# hd-hdr-alt.net
KiCad netlist of a schematic drawn in Altium Designer
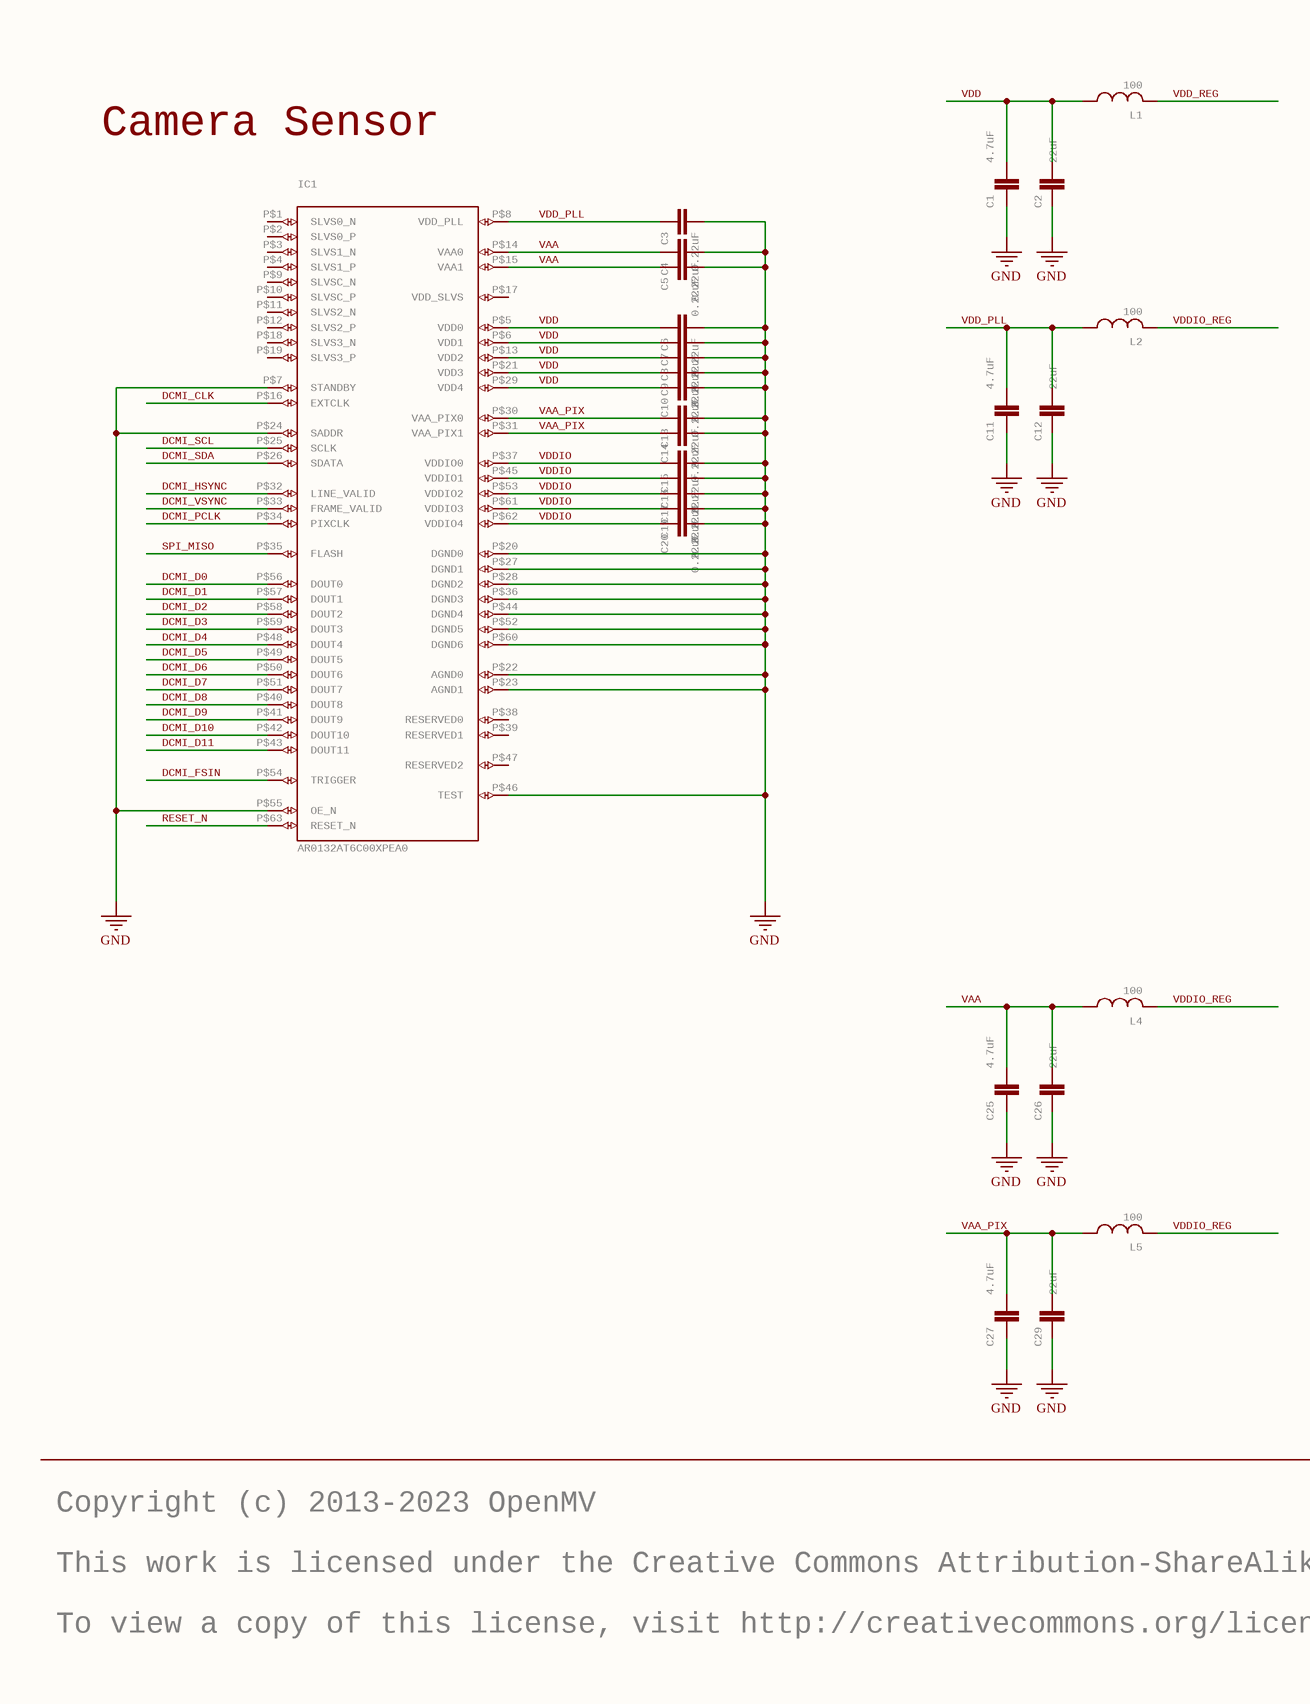
[diagram p0: hd-hdr-alt.SchDoc, left]
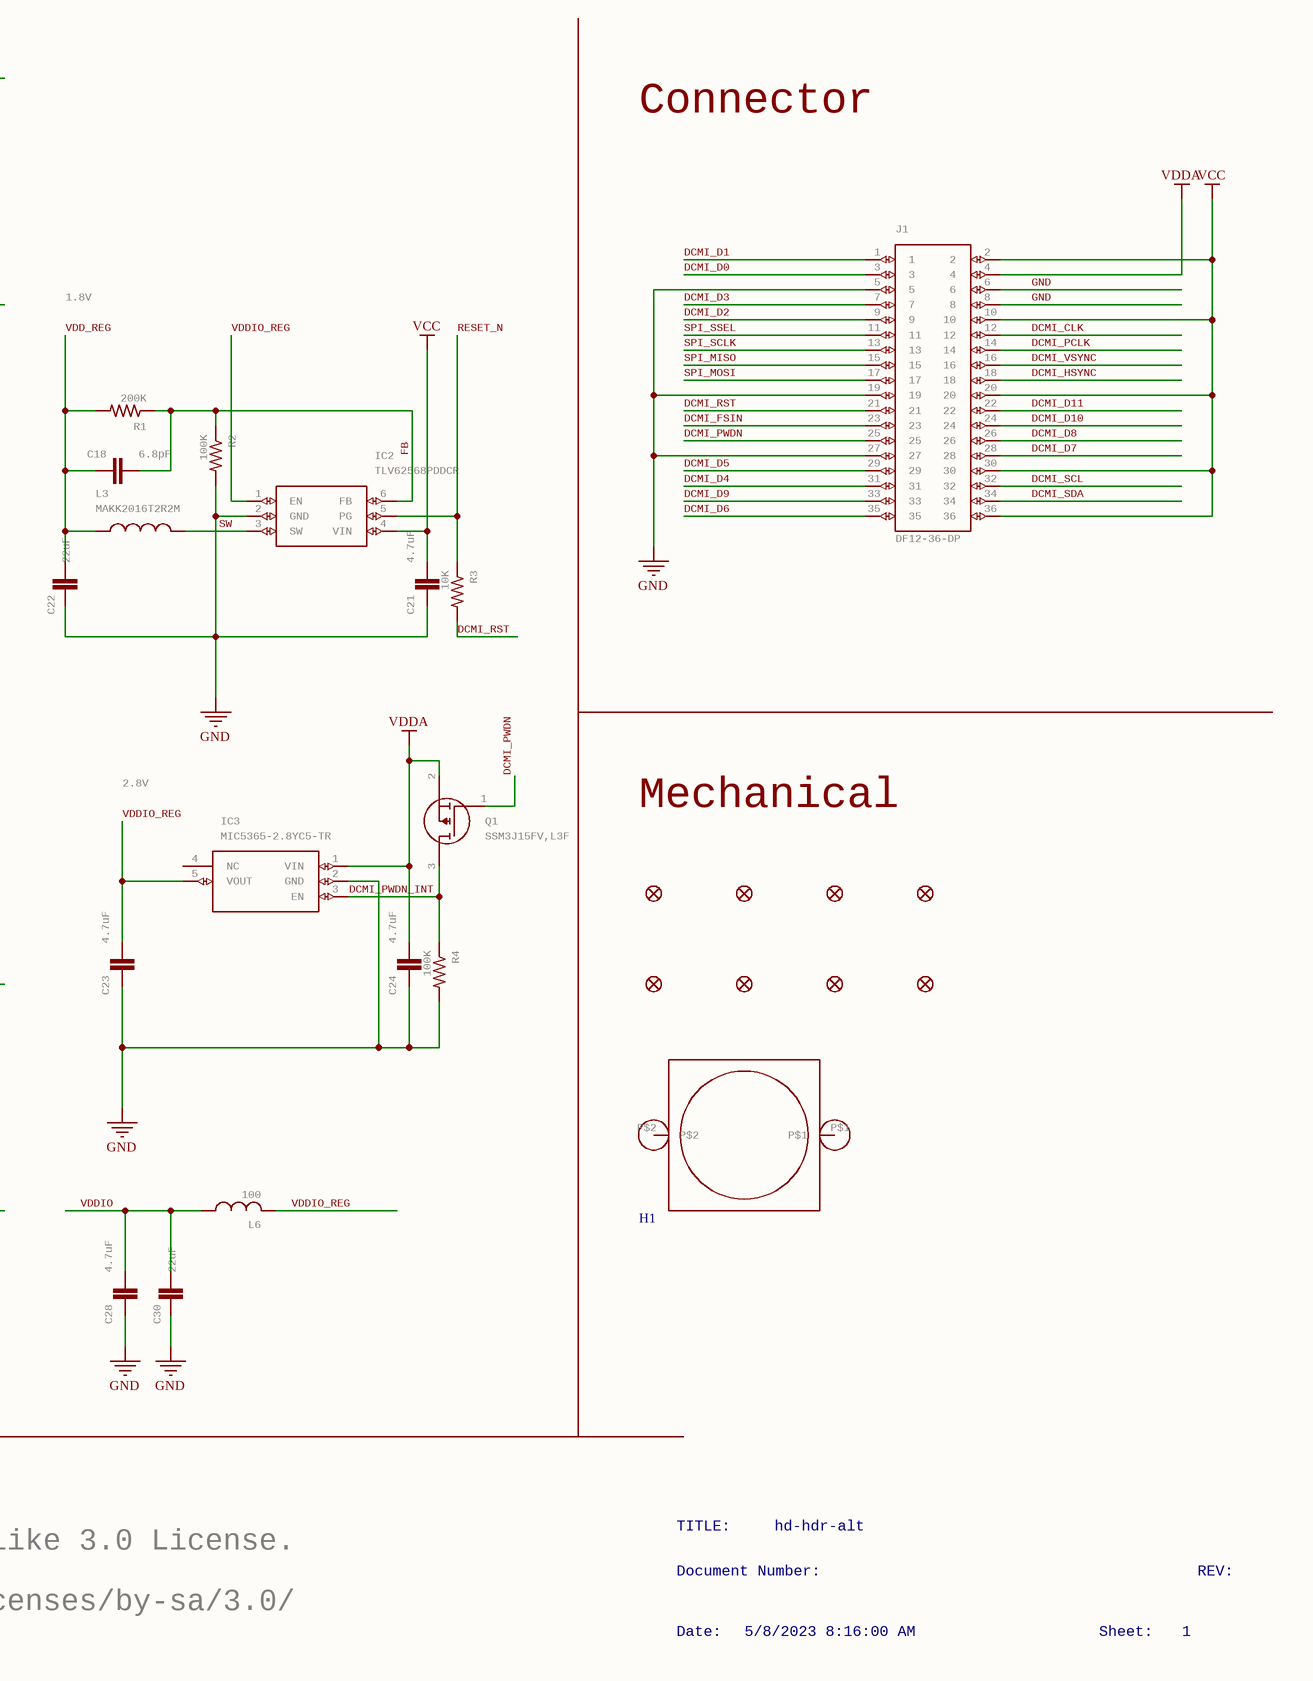
[diagram p1: hd-hdr-alt.SchDoc, right]

(export (version "E")
  (design (tool "Eeschema 10.0.6"))
  (components
    (comp (ref "C1")
      (value "4.7uF")
      (footprint "0402")
      (description "0402 (1005 Metric) Nick Garner - TeleSense")
      (fields (field (name "MPN") "JMK105BBJ475MV-F"))
      (libsource (lib "0402") (part "CAP_0402"))
    )
    (comp (ref "C2")
      (value "22uF")
      (footprint "0805")
      (fields (field (name "MPN") "CL21A226MQQNNNE"))
      (libsource (lib "SparkFun-Capacitors") (part "22UF-0805-6.3V-20%"))
    )
    (comp (ref "C3")
      (value "0.22uF")
      (footprint "C0201")
      (description "CAPACITOR, European symbol")
      (fields (field (name "MPN") "GRM033R60J224ME15D"))
      (libsource (lib "rcl") (part "C-EUC0201"))
    )
    (comp (ref "C4")
      (value "0.22uF")
      (footprint "C0201")
      (description "CAPACITOR, European symbol")
      (fields (field (name "MPN") "GRM033R60J224ME15D"))
      (libsource (lib "rcl") (part "C-EUC0201"))
    )
    (comp (ref "C5")
      (value "0.22uF")
      (footprint "C0201")
      (description "CAPACITOR, European symbol")
      (fields (field (name "MPN") "GRM033R60J224ME15D"))
      (libsource (lib "rcl") (part "C-EUC0201"))
    )
    (comp (ref "C6")
      (value "0.22uF")
      (footprint "C0201")
      (description "CAPACITOR, European symbol")
      (fields (field (name "MPN") "GRM033R60J224ME15D"))
      (libsource (lib "rcl") (part "C-EUC0201"))
    )
    (comp (ref "C7")
      (value "0.22uF")
      (footprint "C0201")
      (description "CAPACITOR, European symbol")
      (fields (field (name "MPN") "GRM033R60J224ME15D"))
      (libsource (lib "rcl") (part "C-EUC0201"))
    )
    (comp (ref "C8")
      (value "0.22uF")
      (footprint "C0201")
      (description "CAPACITOR, European symbol")
      (fields (field (name "MPN") "GRM033R60J224ME15D"))
      (libsource (lib "rcl") (part "C-EUC0201"))
    )
    (comp (ref "C9")
      (value "0.22uF")
      (footprint "C0201")
      (description "CAPACITOR, European symbol")
      (fields (field (name "MPN") "GRM033R60J224ME15D"))
      (libsource (lib "rcl") (part "C-EUC0201"))
    )
    (comp (ref "C10")
      (value "0.22uF")
      (footprint "C0201")
      (description "CAPACITOR, European symbol")
      (fields (field (name "MPN") "GRM033R60J224ME15D"))
      (libsource (lib "rcl") (part "C-EUC0201"))
    )
    (comp (ref "C11")
      (value "4.7uF")
      (footprint "0402")
      (description "0402 (1005 Metric) Nick Garner - TeleSense")
      (fields (field (name "MPN") "JMK105BBJ475MV-F"))
      (libsource (lib "0402") (part "CAP_0402"))
    )
    (comp (ref "C12")
      (value "22uF")
      (footprint "0805")
      (fields (field (name "MPN") "CL21A226MQQNNNE"))
      (libsource (lib "SparkFun-Capacitors") (part "22UF-0805-6.3V-20%"))
    )
    (comp (ref "C13")
      (value "0.22uF")
      (footprint "C0201")
      (description "CAPACITOR, European symbol")
      (fields (field (name "MPN") "GRM033R60J224ME15D"))
      (libsource (lib "rcl") (part "C-EUC0201"))
    )
    (comp (ref "C14")
      (value "0.22uF")
      (footprint "C0201")
      (description "CAPACITOR, European symbol")
      (fields (field (name "MPN") "GRM033R60J224ME15D"))
      (libsource (lib "rcl") (part "C-EUC0201"))
    )
    (comp (ref "C15")
      (value "0.22uF")
      (footprint "C0201")
      (description "CAPACITOR, European symbol")
      (fields (field (name "MPN") "GRM033R60J224ME15D"))
      (libsource (lib "rcl") (part "C-EUC0201"))
    )
    (comp (ref "C16")
      (value "0.22uF")
      (footprint "C0201")
      (description "CAPACITOR, European symbol")
      (fields (field (name "MPN") "GRM033R60J224ME15D"))
      (libsource (lib "rcl") (part "C-EUC0201"))
    )
    (comp (ref "C17")
      (value "0.22uF")
      (footprint "C0201")
      (description "CAPACITOR, European symbol")
      (fields (field (name "MPN") "GRM033R60J224ME15D"))
      (libsource (lib "rcl") (part "C-EUC0201"))
    )
    (comp (ref "C18")
      (value "6.8pF")
      (footprint "0402")
      (description "0402 (1005 Metric) Nick Garner - TeleSense")
      (fields (field (name "MPN") "GRM1555C1H6R8DA01D"))
      (libsource (lib "") (part "CAP_0402_1"))
    )
    (comp (ref "C19")
      (value "0.22uF")
      (footprint "C0201")
      (description "CAPACITOR, European symbol")
      (fields (field (name "MPN") "GRM033R60J224ME15D"))
      (libsource (lib "rcl") (part "C-EUC0201"))
    )
    (comp (ref "C20")
      (value "0.22uF")
      (footprint "C0201")
      (description "CAPACITOR, European symbol")
      (fields (field (name "MPN") "GRM033R60J224ME15D"))
      (libsource (lib "rcl") (part "C-EUC0201"))
    )
    (comp (ref "C21")
      (value "4.7uF")
      (footprint "0402")
      (description "0402 (1005 Metric) Nick Garner - TeleSense")
      (fields (field (name "MPN") "JMK105BBJ475MV-F"))
      (libsource (lib "0402") (part "CAP_0402"))
    )
    (comp (ref "C22")
      (value "22uF")
      (footprint "0805")
      (fields (field (name "MPN") "CL21A226MQQNNNE"))
      (libsource (lib "SparkFun-Capacitors") (part "22UF-0805-6.3V-20%"))
    )
    (comp (ref "C23")
      (value "4.7uF")
      (footprint "0402")
      (description "0402 (1005 Metric) Nick Garner - TeleSense")
      (fields (field (name "MPN") "JMK105BBJ475MV-F"))
      (libsource (lib "0402") (part "CAP_0402"))
    )
    (comp (ref "C24")
      (value "4.7uF")
      (footprint "0402")
      (description "0402 (1005 Metric) Nick Garner - TeleSense")
      (fields (field (name "MPN") "JMK105BBJ475MV-F"))
      (libsource (lib "0402") (part "CAP_0402"))
    )
    (comp (ref "C25")
      (value "4.7uF")
      (footprint "0402")
      (description "0402 (1005 Metric) Nick Garner - TeleSense")
      (fields (field (name "MPN") "JMK105BBJ475MV-F"))
      (libsource (lib "0402") (part "CAP_0402"))
    )
    (comp (ref "C26")
      (value "22uF")
      (footprint "0805")
      (fields (field (name "MPN") "CL21A226MQQNNNE"))
      (libsource (lib "SparkFun-Capacitors") (part "22UF-0805-6.3V-20%"))
    )
    (comp (ref "C27")
      (value "4.7uF")
      (footprint "0402")
      (description "0402 (1005 Metric) Nick Garner - TeleSense")
      (fields (field (name "MPN") "JMK105BBJ475MV-F"))
      (libsource (lib "0402") (part "CAP_0402"))
    )
    (comp (ref "C28")
      (value "4.7uF")
      (footprint "0402")
      (description "0402 (1005 Metric) Nick Garner - TeleSense")
      (fields (field (name "MPN") "JMK105BBJ475MV-F"))
      (libsource (lib "0402") (part "CAP_0402"))
    )
    (comp (ref "C29")
      (value "22uF")
      (footprint "0805")
      (fields (field (name "MPN") "CL21A226MQQNNNE"))
      (libsource (lib "SparkFun-Capacitors") (part "22UF-0805-6.3V-20%"))
    )
    (comp (ref "C30")
      (value "22uF")
      (footprint "0805")
      (fields (field (name "MPN") "CL21A226MQQNNNE"))
      (libsource (lib "SparkFun-Capacitors") (part "22UF-0805-6.3V-20%"))
    )
    (comp (ref "FD1")
      (value "FIDUCIAL1X2")
      (footprint "FIDUCIAL-1X2")
      (fields (field (name "LIBRARYNAME") "SparkFun-Aesthetics"))
      (libsource (lib "SparkFun-Aesthetics") (part "FIDUCIAL1X2"))
    )
    (comp (ref "FD2")
      (value "FIDUCIAL1X2")
      (footprint "FIDUCIAL-1X2")
      (fields (field (name "LIBRARYNAME") "SparkFun-Aesthetics"))
      (libsource (lib "SparkFun-Aesthetics") (part "FIDUCIAL1X2"))
    )
    (comp (ref "FD3")
      (value "FIDUCIAL1X2")
      (footprint "FIDUCIAL-1X2")
      (fields (field (name "LIBRARYNAME") "SparkFun-Aesthetics"))
      (libsource (lib "SparkFun-Aesthetics") (part "FIDUCIAL1X2"))
    )
    (comp (ref "FD4")
      (value "FIDUCIAL1X2")
      (footprint "FIDUCIAL-1X2")
      (fields (field (name "LIBRARYNAME") "SparkFun-Aesthetics"))
      (libsource (lib "SparkFun-Aesthetics") (part "FIDUCIAL1X2"))
    )
    (comp (ref "FD5")
      (value "FIDUCIAL1X2")
      (footprint "FIDUCIAL-1X2")
      (fields (field (name "LIBRARYNAME") "SparkFun-Aesthetics"))
      (libsource (lib "SparkFun-Aesthetics") (part "FIDUCIAL1X2"))
    )
    (comp (ref "FD6")
      (value "FIDUCIAL1X2")
      (footprint "FIDUCIAL-1X2")
      (fields (field (name "LIBRARYNAME") "SparkFun-Aesthetics"))
      (libsource (lib "SparkFun-Aesthetics") (part "FIDUCIAL1X2"))
    )
    (comp (ref "FD7")
      (value "FIDUCIAL1X2")
      (footprint "FIDUCIAL-1X2")
      (fields (field (name "LIBRARYNAME") "SparkFun-Aesthetics"))
      (libsource (lib "SparkFun-Aesthetics") (part "FIDUCIAL1X2"))
    )
    (comp (ref "FD8")
      (value "FIDUCIAL1X2")
      (footprint "FIDUCIAL-1X2")
      (fields (field (name "LIBRARYNAME") "SparkFun-Aesthetics"))
      (libsource (lib "SparkFun-Aesthetics") (part "FIDUCIAL1X2"))
    )
    (comp (ref "H1")
      (value "LENSMOUNT20MM")
      (footprint "LENSMOUNT-20MM")
      (libsource (lib "lensmount") (part "LENSMOUNT20MM"))
    )
    (comp (ref "IC1")
      (value "AR0132AT6C00XPEA0")
      (footprint "AR0132AT6C00XPEA0")
      (fields (field (name "MPN") "AR0132AT6C00XPEA0-TPBR"))
      (libsource (lib "camera-modules") (part "AR0132AT6C00XPEA0"))
    )
    (comp (ref "IC2")
      (value "TLV62568PDDCR")
      (footprint "SOT95P280X110-6N")
      (fields (field (name "MOUSER_PART_NUMBER") "595-TLV62568PDDCR"))
      (libsource (lib "TLV62568PDDCR") (part "TLV62568PDDCR"))
    )
    (comp (ref "IC3")
      (value "MIC5365-2.8YC5-TR")
      (footprint "SOT65P210X110-5N")
      (description "IC REG LINEAR 2.8V 150MA SC70-5   Source:  Datasheet")
      (fields (field (name "MOUSER_PART_NUMBER") "998-MIC5365-2.8YC5TR"))
      (libsource (lib "MIC5365-2.8YC5-TR") (part "MIC5365-2.8YC5-TR"))
    )
    (comp (ref "J1")
      (value "DF12-36-DP")
      (footprint "DF12-36-DP")
      (fields (field (name "MPN") "DF12NB(3.0)-36DP-0.5V(51)"))
      (libsource (lib "DF12NB(3.0)-36DP-0.5V(51)") (part "DF12-36-DP"))
    )
    (comp (ref "L1")
      (value "100")
      (footprint "0402")
      (fields (field (name "MPN") "MFBM1V1005-101-R"))
      (libsource (lib "0402") (part "INDUCTOR_0402"))
    )
    (comp (ref "L2")
      (value "100")
      (footprint "0402")
      (fields (field (name "MPN") "MFBM1V1005-101-R"))
      (libsource (lib "0402") (part "INDUCTOR_0402"))
    )
    (comp (ref "L3")
      (value "MAKK2016T2R2M")
      (footprint "INDC2016X100N")
      (description "INDUCTOR, METAL CORE Check availability")
      (fields (field (name "MF") "Taiyo Yuden"))
      (libsource (lib "MAKK2016T2R2M") (part "MAKK2016T2R2M"))
    )
    (comp (ref "L4")
      (value "100")
      (footprint "0402")
      (fields (field (name "MPN") "MFBM1V1005-101-R"))
      (libsource (lib "0402") (part "INDUCTOR_0402"))
    )
    (comp (ref "L5")
      (value "100")
      (footprint "0402")
      (fields (field (name "MPN") "MFBM1V1005-101-R"))
      (libsource (lib "0402") (part "INDUCTOR_0402"))
    )
    (comp (ref "L6")
      (value "100")
      (footprint "0402")
      (fields (field (name "MPN") "MFBM1V1005-101-R"))
      (libsource (lib "0402") (part "INDUCTOR_0402"))
    )
    (comp (ref "Q1")
      (value "SSM3J15FV,L3F")
      (footprint "SSM3J15FV")
      (libsource (lib "camera-modules") (part "PMOS"))
    )
    (comp (ref "R1")
      (value "200K")
      (footprint "R0402")
      (description "RESISTOR, American symbol")
      (fields (field (name "MPN") "CRCW0402200KFKEDC"))
      (libsource (lib "rcl") (part "R-US_R0402"))
    )
    (comp (ref "R2")
      (value "100K")
      (footprint "R0402")
      (description "RESISTOR, American symbol")
      (fields (field (name "MPN") "AC0402FR-07100KL"))
      (libsource (lib "rcl") (part "R-US_R0402"))
    )
    (comp (ref "R3")
      (value "10K")
      (footprint "R0402")
      (description "RESISTOR, American symbol")
      (fields (field (name "MPN") "AC0402FR-1310KL"))
      (libsource (lib "rcl") (part "R-US_R0402"))
    )
    (comp (ref "R4")
      (value "100K")
      (footprint "R0402")
      (description "RESISTOR, American symbol")
      (fields (field (name "MPN") "AC0402FR-07100KL"))
      (libsource (lib "rcl") (part "R-US_R0402"))
    )
  )
  (nets
    (net (code "1") (name "/DCMI_CLK") (class "Default")
      (node (ref "IC1") (pin "P$16") (pinfunction "EXTCLK_P$16") (pintype "bidirectional"))
      (node (ref "J1") (pin "12") (pinfunction "12_12") (pintype "bidirectional"))
    )
    (net (code "2") (name "/DCMI_D0") (class "Default")
      (node (ref "IC1") (pin "P$56") (pinfunction "DOUT0_P$56") (pintype "bidirectional"))
      (node (ref "J1") (pin "3") (pinfunction "3_3") (pintype "bidirectional"))
    )
    (net (code "3") (name "/DCMI_D1") (class "Default")
      (node (ref "IC1") (pin "P$57") (pinfunction "DOUT1_P$57") (pintype "bidirectional"))
      (node (ref "J1") (pin "1") (pinfunction "1_1") (pintype "bidirectional"))
    )
    (net (code "4") (name "/DCMI_D2") (class "Default")
      (node (ref "IC1") (pin "P$58") (pinfunction "DOUT2_P$58") (pintype "bidirectional"))
      (node (ref "J1") (pin "9") (pinfunction "9_9") (pintype "bidirectional"))
    )
    (net (code "5") (name "/DCMI_D3") (class "Default")
      (node (ref "IC1") (pin "P$59") (pinfunction "DOUT3_P$59") (pintype "bidirectional"))
      (node (ref "J1") (pin "7") (pinfunction "7_7") (pintype "bidirectional"))
    )
    (net (code "6") (name "/DCMI_D4") (class "Default")
      (node (ref "IC1") (pin "P$48") (pinfunction "DOUT4_P$48") (pintype "bidirectional"))
      (node (ref "J1") (pin "31") (pinfunction "31_31") (pintype "bidirectional"))
    )
    (net (code "7") (name "/DCMI_D5") (class "Default")
      (node (ref "IC1") (pin "P$49") (pinfunction "DOUT5_P$49") (pintype "bidirectional"))
      (node (ref "J1") (pin "29") (pinfunction "29_29") (pintype "bidirectional"))
    )
    (net (code "8") (name "/DCMI_D6") (class "Default")
      (node (ref "IC1") (pin "P$50") (pinfunction "DOUT6_P$50") (pintype "bidirectional"))
      (node (ref "J1") (pin "35") (pinfunction "35_35") (pintype "bidirectional"))
    )
    (net (code "9") (name "/DCMI_D7") (class "Default")
      (node (ref "IC1") (pin "P$51") (pinfunction "DOUT7_P$51") (pintype "bidirectional"))
      (node (ref "J1") (pin "28") (pinfunction "28_28") (pintype "bidirectional"))
    )
    (net (code "10") (name "/DCMI_D8") (class "Default")
      (node (ref "IC1") (pin "P$40") (pinfunction "DOUT8_P$40") (pintype "bidirectional"))
      (node (ref "J1") (pin "26") (pinfunction "26_26") (pintype "bidirectional"))
    )
    (net (code "11") (name "/DCMI_D9") (class "Default")
      (node (ref "IC1") (pin "P$41") (pinfunction "DOUT9_P$41") (pintype "bidirectional"))
      (node (ref "J1") (pin "33") (pinfunction "33_33") (pintype "bidirectional"))
    )
    (net (code "12") (name "/DCMI_D10") (class "Default")
      (node (ref "IC1") (pin "P$42") (pinfunction "DOUT10_P$42") (pintype "bidirectional"))
      (node (ref "J1") (pin "24") (pinfunction "24_24") (pintype "bidirectional"))
    )
    (net (code "13") (name "/DCMI_D11") (class "Default")
      (node (ref "IC1") (pin "P$43") (pinfunction "DOUT11_P$43") (pintype "bidirectional"))
      (node (ref "J1") (pin "22") (pinfunction "22_22") (pintype "bidirectional"))
    )
    (net (code "14") (name "/DCMI_FSIN") (class "Default")
      (node (ref "IC1") (pin "P$54") (pinfunction "TRIGGER_P$54") (pintype "bidirectional"))
      (node (ref "J1") (pin "23") (pinfunction "23_23") (pintype "bidirectional"))
    )
    (net (code "15") (name "/DCMI_HSYNC") (class "Default")
      (node (ref "IC1") (pin "P$32") (pinfunction "LINE_VALID_P$32") (pintype "bidirectional"))
      (node (ref "J1") (pin "18") (pinfunction "18_18") (pintype "bidirectional"))
    )
    (net (code "16") (name "/DCMI_PCLK") (class "Default")
      (node (ref "IC1") (pin "P$34") (pinfunction "PIXCLK_P$34") (pintype "bidirectional"))
      (node (ref "J1") (pin "14") (pinfunction "14_14") (pintype "bidirectional"))
    )
    (net (code "17") (name "/DCMI_PWDN") (class "Default")
      (node (ref "J1") (pin "25") (pinfunction "25_25") (pintype "bidirectional"))
      (node (ref "Q1") (pin "1") (pinfunction "G_1") (pintype "bidirectional"))
    )
    (net (code "18") (name "/DCMI_PWDN_INT") (class "Default")
      (node (ref "IC3") (pin "3") (pinfunction "EN_3") (pintype "bidirectional"))
      (node (ref "Q1") (pin "3") (pinfunction "D_3") (pintype "bidirectional"))
      (node (ref "R4") (pin "1") (pinfunction "1_1") (pintype "passive"))
    )
    (net (code "19") (name "/DCMI_RST") (class "Default")
      (node (ref "J1") (pin "21") (pinfunction "21_21") (pintype "bidirectional"))
      (node (ref "R3") (pin "2") (pinfunction "2_2") (pintype "passive"))
    )
    (net (code "20") (name "/DCMI_SCL") (class "Default")
      (node (ref "IC1") (pin "P$25") (pinfunction "SCLK_P$25") (pintype "bidirectional"))
      (node (ref "J1") (pin "32") (pinfunction "32_32") (pintype "bidirectional"))
    )
    (net (code "21") (name "/DCMI_SDA") (class "Default")
      (node (ref "IC1") (pin "P$26") (pinfunction "SDATA_P$26") (pintype "bidirectional"))
      (node (ref "J1") (pin "34") (pinfunction "34_34") (pintype "bidirectional"))
    )
    (net (code "22") (name "/DCMI_VSYNC") (class "Default")
      (node (ref "IC1") (pin "P$33") (pinfunction "FRAME_VALID_P$33") (pintype "bidirectional"))
      (node (ref "J1") (pin "16") (pinfunction "16_16") (pintype "bidirectional"))
    )
    (net (code "23") (name "/FB") (class "Default")
      (node (ref "C18") (pin "2") (pinfunction "2_2") (pintype "passive"))
      (node (ref "IC2") (pin "6") (pinfunction "FB_6") (pintype "bidirectional"))
      (node (ref "R1") (pin "1") (pinfunction "1_1") (pintype "passive"))
      (node (ref "R2") (pin "1") (pinfunction "1_1") (pintype "passive"))
    )
    (net (code "24") (name "/RESET_N") (class "Default")
      (node (ref "IC1") (pin "P$63") (pinfunction "RESET_N_P$63") (pintype "bidirectional"))
      (node (ref "IC2") (pin "5") (pinfunction "PG_5") (pintype "bidirectional"))
      (node (ref "R3") (pin "1") (pinfunction "1_1") (pintype "passive"))
    )
    (net (code "25") (name "/SPI_MISO") (class "Default")
      (node (ref "IC1") (pin "P$35") (pinfunction "FLASH_P$35") (pintype "bidirectional"))
      (node (ref "J1") (pin "15") (pinfunction "15_15") (pintype "bidirectional"))
    )
    (net (code "26") (name "/SPI_MOSI") (class "Default")
      (node (ref "J1") (pin "17") (pinfunction "17_17") (pintype "bidirectional"))
    )
    (net (code "27") (name "/SPI_SCLK") (class "Default")
      (node (ref "J1") (pin "13") (pinfunction "13_13") (pintype "bidirectional"))
    )
    (net (code "28") (name "/SPI_SSEL") (class "Default")
      (node (ref "J1") (pin "11") (pinfunction "11_11") (pintype "bidirectional"))
    )
    (net (code "29") (name "/SW") (class "Default")
      (node (ref "IC2") (pin "3") (pinfunction "SW_3") (pintype "bidirectional"))
      (node (ref "L3") (pin "2") (pinfunction "2_2") (pintype "passive"))
    )
    (net (code "30") (name "/VAA") (class "Default")
      (node (ref "C25") (pin "2") (pinfunction "2_2") (pintype "passive"))
      (node (ref "C26") (pin "2") (pinfunction "2_2") (pintype "passive"))
      (node (ref "C4") (pin "1") (pinfunction "1_1") (pintype "passive"))
      (node (ref "C5") (pin "1") (pinfunction "1_1") (pintype "passive"))
      (node (ref "IC1") (pin "P$14") (pinfunction "VAA0_P$14") (pintype "bidirectional"))
      (node (ref "IC1") (pin "P$15") (pinfunction "VAA1_P$15") (pintype "bidirectional"))
      (node (ref "L4") (pin "1") (pinfunction "P$1_1") (pintype "passive"))
    )
    (net (code "31") (name "/VAA_PIX") (class "Default")
      (node (ref "C13") (pin "1") (pinfunction "1_1") (pintype "passive"))
      (node (ref "C14") (pin "1") (pinfunction "1_1") (pintype "passive"))
      (node (ref "C27") (pin "2") (pinfunction "2_2") (pintype "passive"))
      (node (ref "C29") (pin "2") (pinfunction "2_2") (pintype "passive"))
      (node (ref "IC1") (pin "P$30") (pinfunction "VAA_PIX0_P$30") (pintype "bidirectional"))
      (node (ref "IC1") (pin "P$31") (pinfunction "VAA_PIX1_P$31") (pintype "bidirectional"))
      (node (ref "L5") (pin "1") (pinfunction "P$1_1") (pintype "passive"))
    )
    (net (code "32") (name "/VDD") (class "Default")
      (node (ref "C1") (pin "2") (pinfunction "2_2") (pintype "passive"))
      (node (ref "C10") (pin "1") (pinfunction "1_1") (pintype "passive"))
      (node (ref "C2") (pin "2") (pinfunction "2_2") (pintype "passive"))
      (node (ref "C6") (pin "1") (pinfunction "1_1") (pintype "passive"))
      (node (ref "C7") (pin "1") (pinfunction "1_1") (pintype "passive"))
      (node (ref "C8") (pin "1") (pinfunction "1_1") (pintype "passive"))
      (node (ref "C9") (pin "1") (pinfunction "1_1") (pintype "passive"))
      (node (ref "IC1") (pin "P$13") (pinfunction "VDD2_P$13") (pintype "bidirectional"))
      (node (ref "IC1") (pin "P$21") (pinfunction "VDD3_P$21") (pintype "bidirectional"))
      (node (ref "IC1") (pin "P$29") (pinfunction "VDD4_P$29") (pintype "bidirectional"))
      (node (ref "IC1") (pin "P$5") (pinfunction "VDD0_P$5") (pintype "bidirectional"))
      (node (ref "IC1") (pin "P$6") (pinfunction "VDD1_P$6") (pintype "bidirectional"))
      (node (ref "L1") (pin "1") (pinfunction "P$1_1") (pintype "passive"))
    )
    (net (code "33") (name "/VDDIO") (class "Default")
      (node (ref "C15") (pin "1") (pinfunction "1_1") (pintype "passive"))
      (node (ref "C16") (pin "1") (pinfunction "1_1") (pintype "passive"))
      (node (ref "C17") (pin "1") (pinfunction "1_1") (pintype "passive"))
      (node (ref "C19") (pin "1") (pinfunction "1_1") (pintype "passive"))
      (node (ref "C20") (pin "1") (pinfunction "1_1") (pintype "passive"))
      (node (ref "C28") (pin "2") (pinfunction "2_2") (pintype "passive"))
      (node (ref "C30") (pin "2") (pinfunction "2_2") (pintype "passive"))
      (node (ref "IC1") (pin "P$37") (pinfunction "VDDIO0_P$37") (pintype "bidirectional"))
      (node (ref "IC1") (pin "P$45") (pinfunction "VDDIO1_P$45") (pintype "bidirectional"))
      (node (ref "IC1") (pin "P$53") (pinfunction "VDDIO2_P$53") (pintype "bidirectional"))
      (node (ref "IC1") (pin "P$61") (pinfunction "VDDIO3_P$61") (pintype "bidirectional"))
      (node (ref "IC1") (pin "P$62") (pinfunction "VDDIO4_P$62") (pintype "bidirectional"))
      (node (ref "L6") (pin "1") (pinfunction "P$1_1") (pintype "passive"))
    )
    (net (code "34") (name "/VDDIO_REG") (class "Default")
      (node (ref "C23") (pin "2") (pinfunction "2_2") (pintype "passive"))
      (node (ref "IC2") (pin "1") (pinfunction "EN_1") (pintype "bidirectional"))
      (node (ref "IC3") (pin "5") (pinfunction "VOUT_5") (pintype "bidirectional"))
      (node (ref "L2") (pin "2") (pinfunction "P$2_2") (pintype "passive"))
      (node (ref "L4") (pin "2") (pinfunction "P$2_2") (pintype "passive"))
      (node (ref "L5") (pin "2") (pinfunction "P$2_2") (pintype "passive"))
      (node (ref "L6") (pin "2") (pinfunction "P$2_2") (pintype "passive"))
    )
    (net (code "35") (name "/VDD_PLL") (class "Default")
      (node (ref "C11") (pin "2") (pinfunction "2_2") (pintype "passive"))
      (node (ref "C12") (pin "2") (pinfunction "2_2") (pintype "passive"))
      (node (ref "C3") (pin "1") (pinfunction "1_1") (pintype "passive"))
      (node (ref "IC1") (pin "P$8") (pinfunction "VDD_PLL_P$8") (pintype "bidirectional"))
      (node (ref "L2") (pin "1") (pinfunction "P$1_1") (pintype "passive"))
    )
    (net (code "36") (name "/VDD_REG") (class "Default")
      (node (ref "C18") (pin "1") (pinfunction "1_1") (pintype "passive"))
      (node (ref "C22") (pin "2") (pinfunction "2_2") (pintype "passive"))
      (node (ref "L1") (pin "2") (pinfunction "P$2_2") (pintype "passive"))
      (node (ref "L3") (pin "1") (pinfunction "1_1") (pintype "passive"))
      (node (ref "R1") (pin "2") (pinfunction "2_2") (pintype "passive"))
    )
    (net (code "37") (name "GND") (class "Default")
      (node (ref "C1") (pin "1") (pinfunction "1_1") (pintype "passive"))
      (node (ref "C10") (pin "2") (pinfunction "2_2") (pintype "passive"))
      (node (ref "C11") (pin "1") (pinfunction "1_1") (pintype "passive"))
      (node (ref "C12") (pin "1") (pinfunction "1_1") (pintype "passive"))
      (node (ref "C13") (pin "2") (pinfunction "2_2") (pintype "passive"))
      (node (ref "C14") (pin "2") (pinfunction "2_2") (pintype "passive"))
      (node (ref "C15") (pin "2") (pinfunction "2_2") (pintype "passive"))
      (node (ref "C16") (pin "2") (pinfunction "2_2") (pintype "passive"))
      (node (ref "C17") (pin "2") (pinfunction "2_2") (pintype "passive"))
      (node (ref "C19") (pin "2") (pinfunction "2_2") (pintype "passive"))
      (node (ref "C2") (pin "1") (pinfunction "1_1") (pintype "passive"))
      (node (ref "C20") (pin "2") (pinfunction "2_2") (pintype "passive"))
      (node (ref "C21") (pin "1") (pinfunction "1_1") (pintype "passive"))
      (node (ref "C22") (pin "1") (pinfunction "1_1") (pintype "passive"))
      (node (ref "C23") (pin "1") (pinfunction "1_1") (pintype "passive"))
      (node (ref "C24") (pin "1") (pinfunction "1_1") (pintype "passive"))
      (node (ref "C25") (pin "1") (pinfunction "1_1") (pintype "passive"))
      (node (ref "C26") (pin "1") (pinfunction "1_1") (pintype "passive"))
      (node (ref "C27") (pin "1") (pinfunction "1_1") (pintype "passive"))
      (node (ref "C28") (pin "1") (pinfunction "1_1") (pintype "passive"))
      (node (ref "C29") (pin "1") (pinfunction "1_1") (pintype "passive"))
      (node (ref "C3") (pin "2") (pinfunction "2_2") (pintype "passive"))
      (node (ref "C30") (pin "1") (pinfunction "1_1") (pintype "passive"))
      (node (ref "C4") (pin "2") (pinfunction "2_2") (pintype "passive"))
      (node (ref "C5") (pin "2") (pinfunction "2_2") (pintype "passive"))
      (node (ref "C6") (pin "2") (pinfunction "2_2") (pintype "passive"))
      (node (ref "C7") (pin "2") (pinfunction "2_2") (pintype "passive"))
      (node (ref "C8") (pin "2") (pinfunction "2_2") (pintype "passive"))
      (node (ref "C9") (pin "2") (pinfunction "2_2") (pintype "passive"))
      (node (ref "IC1") (pin "P$20") (pinfunction "DGND0_P$20") (pintype "bidirectional"))
      (node (ref "IC1") (pin "P$22") (pinfunction "AGND0_P$22") (pintype "bidirectional"))
      (node (ref "IC1") (pin "P$23") (pinfunction "AGND1_P$23") (pintype "bidirectional"))
      (node (ref "IC1") (pin "P$24") (pinfunction "SADDR_P$24") (pintype "bidirectional"))
      (node (ref "IC1") (pin "P$27") (pinfunction "DGND1_P$27") (pintype "bidirectional"))
      (node (ref "IC1") (pin "P$28") (pinfunction "DGND2_P$28") (pintype "bidirectional"))
      (node (ref "IC1") (pin "P$36") (pinfunction "DGND3_P$36") (pintype "bidirectional"))
      (node (ref "IC1") (pin "P$44") (pinfunction "DGND4_P$44") (pintype "bidirectional"))
      (node (ref "IC1") (pin "P$46") (pinfunction "TEST_P$46") (pintype "bidirectional"))
      (node (ref "IC1") (pin "P$52") (pinfunction "DGND5_P$52") (pintype "bidirectional"))
      (node (ref "IC1") (pin "P$55") (pinfunction "OE_N_P$55") (pintype "bidirectional"))
      (node (ref "IC1") (pin "P$60") (pinfunction "DGND6_P$60") (pintype "bidirectional"))
      (node (ref "IC1") (pin "P$7") (pinfunction "STANDBY_P$7") (pintype "bidirectional"))
      (node (ref "IC2") (pin "2") (pinfunction "GND_2") (pintype "bidirectional"))
      (node (ref "IC3") (pin "2") (pinfunction "GND_2") (pintype "bidirectional"))
      (node (ref "J1") (pin "19") (pinfunction "19_19") (pintype "bidirectional"))
      (node (ref "J1") (pin "27") (pinfunction "27_27") (pintype "bidirectional"))
      (node (ref "J1") (pin "5") (pinfunction "5_5") (pintype "bidirectional"))
      (node (ref "J1") (pin "6") (pinfunction "6_6") (pintype "bidirectional"))
      (node (ref "J1") (pin "8") (pinfunction "8_8") (pintype "bidirectional"))
      (node (ref "R2") (pin "2") (pinfunction "2_2") (pintype "passive"))
      (node (ref "R4") (pin "2") (pinfunction "2_2") (pintype "passive"))
    )
    (net (code "38") (name "VCC") (class "Default")
      (node (ref "C21") (pin "2") (pinfunction "2_2") (pintype "passive"))
      (node (ref "IC2") (pin "4") (pinfunction "VIN_4") (pintype "bidirectional"))
      (node (ref "J1") (pin "10") (pinfunction "10_10") (pintype "bidirectional"))
      (node (ref "J1") (pin "2") (pinfunction "2_2") (pintype "bidirectional"))
      (node (ref "J1") (pin "20") (pinfunction "20_20") (pintype "bidirectional"))
      (node (ref "J1") (pin "30") (pinfunction "30_30") (pintype "bidirectional"))
      (node (ref "J1") (pin "36") (pinfunction "36_36") (pintype "bidirectional"))
    )
    (net (code "39") (name "VDDA") (class "Default")
      (node (ref "C24") (pin "2") (pinfunction "2_2") (pintype "passive"))
      (node (ref "IC3") (pin "1") (pinfunction "VIN_1") (pintype "bidirectional"))
      (node (ref "J1") (pin "4") (pinfunction "4_4") (pintype "bidirectional"))
      (node (ref "Q1") (pin "2") (pinfunction "S_2") (pintype "bidirectional"))
    )
    (net (code "40") (name "unconnected-(H1-PadP$1)") (class "Default")
      (node (ref "H1") (pin "P$1") (pinfunction "P$1_P$1") (pintype "power_in"))
    )
    (net (code "41") (name "unconnected-(H1-PadP$2)") (class "Default")
      (node (ref "H1") (pin "P$2") (pinfunction "P$2_P$2") (pintype "power_in"))
    )
    (net (code "42") (name "unconnected-(IC1-RESERVED0-PadP$38)") (class "Default")
      (node (ref "IC1") (pin "P$38") (pinfunction "RESERVED0_P$38") (pintype "bidirectional"))
    )
    (net (code "43") (name "unconnected-(IC1-RESERVED1-PadP$39)") (class "Default")
      (node (ref "IC1") (pin "P$39") (pinfunction "RESERVED1_P$39") (pintype "bidirectional"))
    )
    (net (code "44") (name "unconnected-(IC1-RESERVED2-PadP$47)") (class "Default")
      (node (ref "IC1") (pin "P$47") (pinfunction "RESERVED2_P$47") (pintype "bidirectional"))
    )
    (net (code "45") (name "unconnected-(IC1-SLVS0_N-PadP$1)") (class "Default")
      (node (ref "IC1") (pin "P$1") (pinfunction "SLVS0_N_P$1") (pintype "bidirectional"))
    )
    (net (code "46") (name "unconnected-(IC1-SLVS0_P-PadP$2)") (class "Default")
      (node (ref "IC1") (pin "P$2") (pinfunction "SLVS0_P_P$2") (pintype "bidirectional"))
    )
    (net (code "47") (name "unconnected-(IC1-SLVS1_N-PadP$3)") (class "Default")
      (node (ref "IC1") (pin "P$3") (pinfunction "SLVS1_N_P$3") (pintype "bidirectional"))
    )
    (net (code "48") (name "unconnected-(IC1-SLVS1_P-PadP$4)") (class "Default")
      (node (ref "IC1") (pin "P$4") (pinfunction "SLVS1_P_P$4") (pintype "bidirectional"))
    )
    (net (code "49") (name "unconnected-(IC1-SLVS2_N-PadP$11)") (class "Default")
      (node (ref "IC1") (pin "P$11") (pinfunction "SLVS2_N_P$11") (pintype "bidirectional"))
    )
    (net (code "50") (name "unconnected-(IC1-SLVS2_P-PadP$12)") (class "Default")
      (node (ref "IC1") (pin "P$12") (pinfunction "SLVS2_P_P$12") (pintype "bidirectional"))
    )
    (net (code "51") (name "unconnected-(IC1-SLVS3_N-PadP$18)") (class "Default")
      (node (ref "IC1") (pin "P$18") (pinfunction "SLVS3_N_P$18") (pintype "bidirectional"))
    )
    (net (code "52") (name "unconnected-(IC1-SLVS3_P-PadP$19)") (class "Default")
      (node (ref "IC1") (pin "P$19") (pinfunction "SLVS3_P_P$19") (pintype "bidirectional"))
    )
    (net (code "53") (name "unconnected-(IC1-SLVSC_N-PadP$9)") (class "Default")
      (node (ref "IC1") (pin "P$9") (pinfunction "SLVSC_N_P$9") (pintype "bidirectional"))
    )
    (net (code "54") (name "unconnected-(IC1-SLVSC_P-PadP$10)") (class "Default")
      (node (ref "IC1") (pin "P$10") (pinfunction "SLVSC_P_P$10") (pintype "bidirectional"))
    )
    (net (code "55") (name "unconnected-(IC1-VDD_SLVS-PadP$17)") (class "Default")
      (node (ref "IC1") (pin "P$17") (pinfunction "VDD_SLVS_P$17") (pintype "bidirectional"))
    )
    (net (code "56") (name "unconnected-(IC3-NC-Pad4)") (class "Default")
      (node (ref "IC3") (pin "4") (pinfunction "NC_4") (pintype "passive"))
    )
  )
)
